# Temperature_and_Humidity_tester.net
KiCad netlist of a schematic drawn in EAGLE
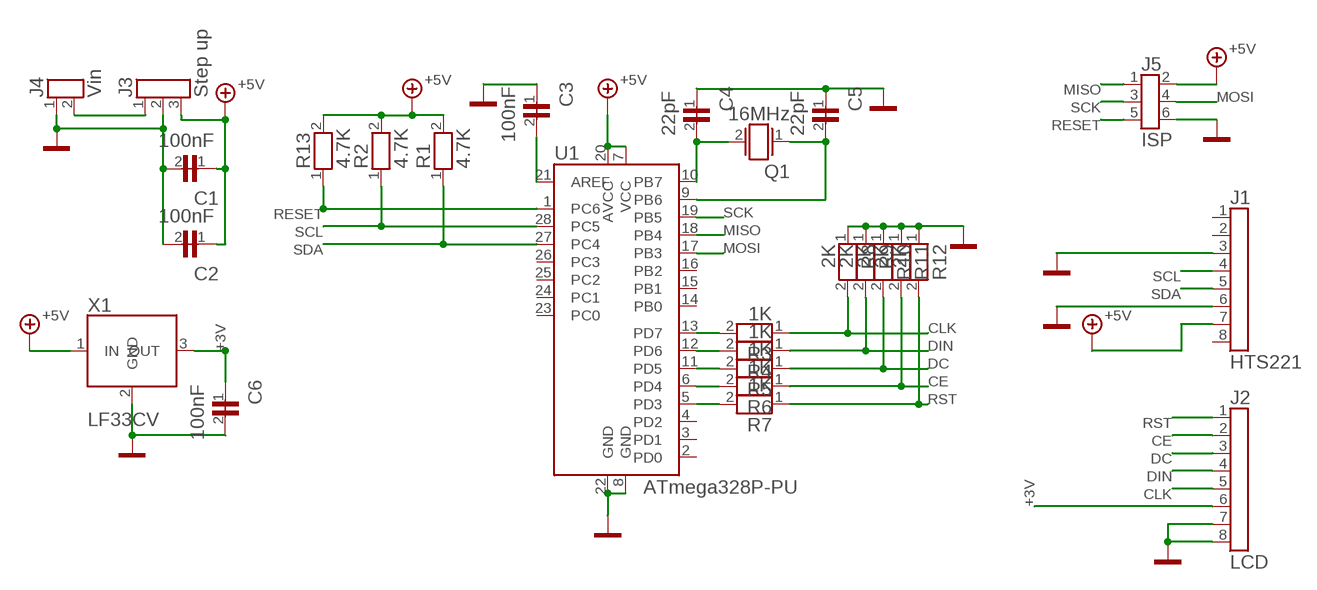
[diagram p0: schematic, sheet 1]

(export (version "E")
  (design (tool "Eeschema 10.0.6"))
  (components
    (comp (ref "C1")
      (value "100nF")
      (footprint "eagle-import:3X5R2,54_42")
      (libsource (lib "eagle-import") (part "B37982-N5104-M_42"))
    )
    (comp (ref "C2")
      (value "100nF")
      (footprint "eagle-import:3X5R2,54_43")
      (libsource (lib "eagle-import") (part "B37982-N5104-M_43"))
    )
    (comp (ref "C3")
      (value "100nF")
      (footprint "eagle-import:3X5R2,54_44")
      (libsource (lib "eagle-import") (part "B37982-N5104-M_44"))
    )
    (comp (ref "C4")
      (value "22pF")
      (footprint "eagle-import:6X6R2,54_DISC_47")
      (libsource (lib "eagle-import") (part "C-CERAMIC-2,54_100V_2%_22PF_47"))
    )
    (comp (ref "C5")
      (value "22pF")
      (footprint "eagle-import:6X6R2,54_DISC_48")
      (libsource (lib "eagle-import") (part "C-CERAMIC-2,54_100V_2%_22PF_48"))
    )
    (comp (ref "C6")
      (value "100nF")
      (footprint "eagle-import:3X5R2,54_66")
      (libsource (lib "eagle-import") (part "B37982-N5104-M_66"))
    )
    (comp (ref "J1")
      (value "HTS221")
      (footprint "eagle-import:STIFTLEISTE_1X08_G_2,54_1")
      (libsource (lib "eagle-import") (part "PINHEADER_1X08_G_2,54_1"))
    )
    (comp (ref "J2")
      (value "LCD")
      (footprint "eagle-import:STIFTLEISTE_1X08_G_2,54_2")
      (libsource (lib "eagle-import") (part "PINHEADER_1X08_G_2,54_2"))
    )
    (comp (ref "J3")
      (value "Step up")
      (footprint "eagle-import:STIFTLEISTE_1X03_G_2,54_3")
      (libsource (lib "eagle-import") (part "PINHEADER_1X03_G_2,54_3"))
    )
    (comp (ref "J4")
      (value "Vin")
      (footprint "eagle-import:STIFTLEISTE_1X02_G_2,54_4")
      (libsource (lib "eagle-import") (part "PINHEADER_1X02_G_2,54_4"))
    )
    (comp (ref "J5")
      (value "ISP")
      (footprint "eagle-import:STIFTLEISTE_2X03_G_2,54_59")
      (libsource (lib "eagle-import") (part "PINHEADER_2X03_G_2,54_59"))
    )
    (comp (ref "Q1")
      (value "16MHz")
      (footprint "eagle-import:HC49_U_46")
      (libsource (lib "eagle-import") (part "LFXTAL003231_46"))
    )
    (comp (ref "R1")
      (value "4.7K")
      (footprint "eagle-import:0204_MET_27")
      (libsource (lib "eagle-import") (part "R_MET_10K_0204_27"))
    )
    (comp (ref "R2")
      (value "4.7K")
      (footprint "eagle-import:0204_MET_28")
      (libsource (lib "eagle-import") (part "R_MET_10K_0204_28"))
    )
    (comp (ref "R3")
      (value "1K")
      (footprint "eagle-import:0204_MET_31")
      (libsource (lib "eagle-import") (part "R_MET_10K_0204_31"))
    )
    (comp (ref "R4")
      (value "1K")
      (footprint "eagle-import:0204_MET_32")
      (libsource (lib "eagle-import") (part "R_MET_10K_0204_32"))
    )
    (comp (ref "R5")
      (value "1K")
      (footprint "eagle-import:0204_MET_33")
      (libsource (lib "eagle-import") (part "R_MET_10K_0204_33"))
    )
    (comp (ref "R6")
      (value "1K")
      (footprint "eagle-import:0204_MET_34")
      (libsource (lib "eagle-import") (part "R_MET_10K_0204_34"))
    )
    (comp (ref "R7")
      (value "1K")
      (footprint "eagle-import:0204_MET_35")
      (libsource (lib "eagle-import") (part "R_MET_10K_0204_35"))
    )
    (comp (ref "R8")
      (value "2K")
      (footprint "eagle-import:0204_MET_36")
      (libsource (lib "eagle-import") (part "R_MET_10K_0204_36"))
    )
    (comp (ref "R9")
      (value "2K")
      (footprint "eagle-import:0204_MET_37")
      (libsource (lib "eagle-import") (part "R_MET_10K_0204_37"))
    )
    (comp (ref "R10")
      (value "2K")
      (footprint "eagle-import:0204_MET_38")
      (libsource (lib "eagle-import") (part "R_MET_10K_0204_38"))
    )
    (comp (ref "R11")
      (value "2K")
      (footprint "eagle-import:0204_MET_39")
      (libsource (lib "eagle-import") (part "R_MET_10K_0204_39"))
    )
    (comp (ref "R12")
      (value "2K")
      (footprint "eagle-import:0204_MET_40")
      (libsource (lib "eagle-import") (part "R_MET_10K_0204_40"))
    )
    (comp (ref "R13")
      (value "4.7K")
      (footprint "eagle-import:0204_MET_57")
      (libsource (lib "eagle-import") (part "R_MET_10K_0204_57"))
    )
    (comp (ref "U1")
      (value "ATmega328P-PU")
      (footprint "eagle-import:DIL28_WB7,62_P2,54_0")
      (libsource (lib "eagle-import") (part "ATMEGA328P-PU_0"))
    )
    (comp (ref "X1")
      (value "LF33CV")
      (footprint "eagle-import:TO220_62")
      (libsource (lib "eagle-import") (part "LF33CV_62"))
    )
  )
  (nets
    (net (code "1") (name "+5V") (class "Default")
      (node (ref "C1") (pin "1") (pinfunction "1_1") (pintype "passive"))
      (node (ref "C2") (pin "1") (pinfunction "1_1") (pintype "passive"))
      (node (ref "J1") (pin "7") (pinfunction "7_7") (pintype "passive"))
      (node (ref "J3") (pin "3") (pinfunction "3_3") (pintype "passive"))
      (node (ref "J5") (pin "2") (pinfunction "2_2") (pintype "passive"))
      (node (ref "R1") (pin "2") (pinfunction "2_2") (pintype "passive"))
      (node (ref "R13") (pin "2") (pinfunction "2_2") (pintype "passive"))
      (node (ref "R2") (pin "2") (pinfunction "2_2") (pintype "passive"))
      (node (ref "U1") (pin "20") (pinfunction "AVCC_20") (pintype "power_in"))
      (node (ref "U1") (pin "7") (pinfunction "VCC_7") (pintype "power_in"))
      (node (ref "X1") (pin "1") (pinfunction "IN_1") (pintype "power_in"))
    )
    (net (code "2") (name "/+3V") (class "Default")
      (node (ref "C6") (pin "1") (pinfunction "1_1") (pintype "passive"))
      (node (ref "J2") (pin "6") (pinfunction "6_6") (pintype "passive"))
      (node (ref "X1") (pin "3") (pinfunction "OUT_3") (pintype "power_in"))
    )
    (net (code "3") (name "/CE") (class "Default")
      (node (ref "J2") (pin "2") (pinfunction "2_2") (pintype "passive"))
      (node (ref "R11") (pin "2") (pinfunction "2_2") (pintype "passive"))
      (node (ref "R6") (pin "1") (pinfunction "1_1") (pintype "passive"))
    )
    (net (code "4") (name "/CLK") (class "Default")
      (node (ref "J2") (pin "5") (pinfunction "5_5") (pintype "passive"))
      (node (ref "R3") (pin "1") (pinfunction "1_1") (pintype "passive"))
      (node (ref "R8") (pin "2") (pinfunction "2_2") (pintype "passive"))
    )
    (net (code "5") (name "/DC") (class "Default")
      (node (ref "J2") (pin "3") (pinfunction "3_3") (pintype "passive"))
      (node (ref "R10") (pin "2") (pinfunction "2_2") (pintype "passive"))
      (node (ref "R5") (pin "1") (pinfunction "1_1") (pintype "passive"))
    )
    (net (code "6") (name "/DIN") (class "Default")
      (node (ref "J2") (pin "4") (pinfunction "4_4") (pintype "passive"))
      (node (ref "R4") (pin "1") (pinfunction "1_1") (pintype "passive"))
      (node (ref "R9") (pin "2") (pinfunction "2_2") (pintype "passive"))
    )
    (net (code "7") (name "/MISO") (class "Default")
      (node (ref "J5") (pin "1") (pinfunction "1_1") (pintype "passive"))
      (node (ref "U1") (pin "18") (pinfunction "PB4_18") (pintype "bidirectional"))
    )
    (net (code "8") (name "/MOSI") (class "Default")
      (node (ref "J5") (pin "4") (pinfunction "4_4") (pintype "passive"))
      (node (ref "U1") (pin "17") (pinfunction "PB3_17") (pintype "bidirectional"))
    )
    (net (code "9") (name "/RESET") (class "Default")
      (node (ref "J5") (pin "5") (pinfunction "5_5") (pintype "passive"))
      (node (ref "R13") (pin "1") (pinfunction "1_1") (pintype "passive"))
      (node (ref "U1") (pin "1") (pinfunction "PC6_1") (pintype "bidirectional"))
    )
    (net (code "10") (name "/RST") (class "Default")
      (node (ref "J2") (pin "1") (pinfunction "1_1") (pintype "passive"))
      (node (ref "R12") (pin "2") (pinfunction "2_2") (pintype "passive"))
      (node (ref "R7") (pin "1") (pinfunction "1_1") (pintype "passive"))
    )
    (net (code "11") (name "/SCK") (class "Default")
      (node (ref "J5") (pin "3") (pinfunction "3_3") (pintype "passive"))
      (node (ref "U1") (pin "19") (pinfunction "PB5_19") (pintype "bidirectional"))
    )
    (net (code "12") (name "/SCL") (class "Default")
      (node (ref "J1") (pin "4") (pinfunction "4_4") (pintype "passive"))
      (node (ref "R2") (pin "1") (pinfunction "1_1") (pintype "passive"))
      (node (ref "U1") (pin "28") (pinfunction "PC5_28") (pintype "bidirectional"))
    )
    (net (code "13") (name "/SDA") (class "Default")
      (node (ref "J1") (pin "5") (pinfunction "5_5") (pintype "passive"))
      (node (ref "R1") (pin "1") (pinfunction "1_1") (pintype "passive"))
      (node (ref "U1") (pin "27") (pinfunction "PC4_27") (pintype "bidirectional"))
    )
    (net (code "14") (name "GND") (class "Default")
      (node (ref "C1") (pin "2") (pinfunction "2_2") (pintype "passive"))
      (node (ref "C2") (pin "2") (pinfunction "2_2") (pintype "passive"))
      (node (ref "C3") (pin "1") (pinfunction "1_1") (pintype "passive"))
      (node (ref "C4") (pin "1") (pinfunction "1_1") (pintype "passive"))
      (node (ref "C5") (pin "1") (pinfunction "1_1") (pintype "passive"))
      (node (ref "C6") (pin "2") (pinfunction "2_2") (pintype "passive"))
      (node (ref "J1") (pin "3") (pinfunction "3_3") (pintype "passive"))
      (node (ref "J1") (pin "6") (pinfunction "6_6") (pintype "passive"))
      (node (ref "J2") (pin "7") (pinfunction "7_7") (pintype "passive"))
      (node (ref "J2") (pin "8") (pinfunction "8_8") (pintype "passive"))
      (node (ref "J3") (pin "2") (pinfunction "2_2") (pintype "passive"))
      (node (ref "J4") (pin "1") (pinfunction "1_1") (pintype "passive"))
      (node (ref "J5") (pin "6") (pinfunction "6_6") (pintype "passive"))
      (node (ref "R10") (pin "1") (pinfunction "1_1") (pintype "passive"))
      (node (ref "R11") (pin "1") (pinfunction "1_1") (pintype "passive"))
      (node (ref "R12") (pin "1") (pinfunction "1_1") (pintype "passive"))
      (node (ref "R8") (pin "1") (pinfunction "1_1") (pintype "passive"))
      (node (ref "R9") (pin "1") (pinfunction "1_1") (pintype "passive"))
      (node (ref "U1") (pin "22") (pinfunction "GND_22") (pintype "power_in"))
      (node (ref "U1") (pin "8") (pinfunction "GND_8") (pintype "power_in"))
      (node (ref "X1") (pin "2") (pinfunction "GND_2") (pintype "power_in"))
    )
    (net (code "15") (name "Net-(J3-Pad1)") (class "Default")
      (node (ref "J3") (pin "1") (pinfunction "1_1") (pintype "passive"))
      (node (ref "J4") (pin "2") (pinfunction "2_2") (pintype "passive"))
    )
    (net (code "16") (name "Net-(U1-AREF)") (class "Default")
      (node (ref "C3") (pin "2") (pinfunction "2_2") (pintype "passive"))
      (node (ref "U1") (pin "21") (pinfunction "AREF_21") (pintype "passive"))
    )
    (net (code "17") (name "Net-(U1-PB6)") (class "Default")
      (node (ref "C5") (pin "2") (pinfunction "2_2") (pintype "passive"))
      (node (ref "Q1") (pin "1") (pinfunction "1_1") (pintype "passive"))
      (node (ref "U1") (pin "9") (pinfunction "PB6_9") (pintype "bidirectional"))
    )
    (net (code "18") (name "Net-(U1-PB7)") (class "Default")
      (node (ref "C4") (pin "2") (pinfunction "2_2") (pintype "passive"))
      (node (ref "Q1") (pin "2") (pinfunction "2_2") (pintype "passive"))
      (node (ref "U1") (pin "10") (pinfunction "PB7_10") (pintype "bidirectional"))
    )
    (net (code "19") (name "Net-(U1-PD3)") (class "Default")
      (node (ref "R7") (pin "2") (pinfunction "2_2") (pintype "passive"))
      (node (ref "U1") (pin "5") (pinfunction "PD3_5") (pintype "bidirectional"))
    )
    (net (code "20") (name "Net-(U1-PD4)") (class "Default")
      (node (ref "R6") (pin "2") (pinfunction "2_2") (pintype "passive"))
      (node (ref "U1") (pin "6") (pinfunction "PD4_6") (pintype "bidirectional"))
    )
    (net (code "21") (name "Net-(U1-PD5)") (class "Default")
      (node (ref "R5") (pin "2") (pinfunction "2_2") (pintype "passive"))
      (node (ref "U1") (pin "11") (pinfunction "PD5_11") (pintype "bidirectional"))
    )
    (net (code "22") (name "Net-(U1-PD6)") (class "Default")
      (node (ref "R4") (pin "2") (pinfunction "2_2") (pintype "passive"))
      (node (ref "U1") (pin "12") (pinfunction "PD6_12") (pintype "bidirectional"))
    )
    (net (code "23") (name "Net-(U1-PD7)") (class "Default")
      (node (ref "R3") (pin "2") (pinfunction "2_2") (pintype "passive"))
      (node (ref "U1") (pin "13") (pinfunction "PD7_13") (pintype "bidirectional"))
    )
    (net (code "24") (name "unconnected-(J1-Pad1)") (class "Default")
      (node (ref "J1") (pin "1") (pinfunction "1_1") (pintype "passive"))
    )
    (net (code "25") (name "unconnected-(J1-Pad2)") (class "Default")
      (node (ref "J1") (pin "2") (pinfunction "2_2") (pintype "passive"))
    )
    (net (code "26") (name "unconnected-(J1-Pad8)") (class "Default")
      (node (ref "J1") (pin "8") (pinfunction "8_8") (pintype "passive"))
    )
    (net (code "27") (name "unconnected-(U1-PB0-Pad14)") (class "Default")
      (node (ref "U1") (pin "14") (pinfunction "PB0_14") (pintype "bidirectional"))
    )
    (net (code "28") (name "unconnected-(U1-PB1-Pad15)") (class "Default")
      (node (ref "U1") (pin "15") (pinfunction "PB1_15") (pintype "bidirectional"))
    )
    (net (code "29") (name "unconnected-(U1-PB2-Pad16)") (class "Default")
      (node (ref "U1") (pin "16") (pinfunction "PB2_16") (pintype "bidirectional"))
    )
    (net (code "30") (name "unconnected-(U1-PC0-Pad23)") (class "Default")
      (node (ref "U1") (pin "23") (pinfunction "PC0_23") (pintype "bidirectional"))
    )
    (net (code "31") (name "unconnected-(U1-PC1-Pad24)") (class "Default")
      (node (ref "U1") (pin "24") (pinfunction "PC1_24") (pintype "bidirectional"))
    )
    (net (code "32") (name "unconnected-(U1-PC2-Pad25)") (class "Default")
      (node (ref "U1") (pin "25") (pinfunction "PC2_25") (pintype "bidirectional"))
    )
    (net (code "33") (name "unconnected-(U1-PC3-Pad26)") (class "Default")
      (node (ref "U1") (pin "26") (pinfunction "PC3_26") (pintype "bidirectional"))
    )
    (net (code "34") (name "unconnected-(U1-PD0-Pad2)") (class "Default")
      (node (ref "U1") (pin "2") (pinfunction "PD0_2") (pintype "bidirectional"))
    )
    (net (code "35") (name "unconnected-(U1-PD1-Pad3)") (class "Default")
      (node (ref "U1") (pin "3") (pinfunction "PD1_3") (pintype "bidirectional"))
    )
    (net (code "36") (name "unconnected-(U1-PD2-Pad4)") (class "Default")
      (node (ref "U1") (pin "4") (pinfunction "PD2_4") (pintype "bidirectional"))
    )
  )
)
